# Connector.net
KiCad netlist of a schematic drawn in Altium Designer
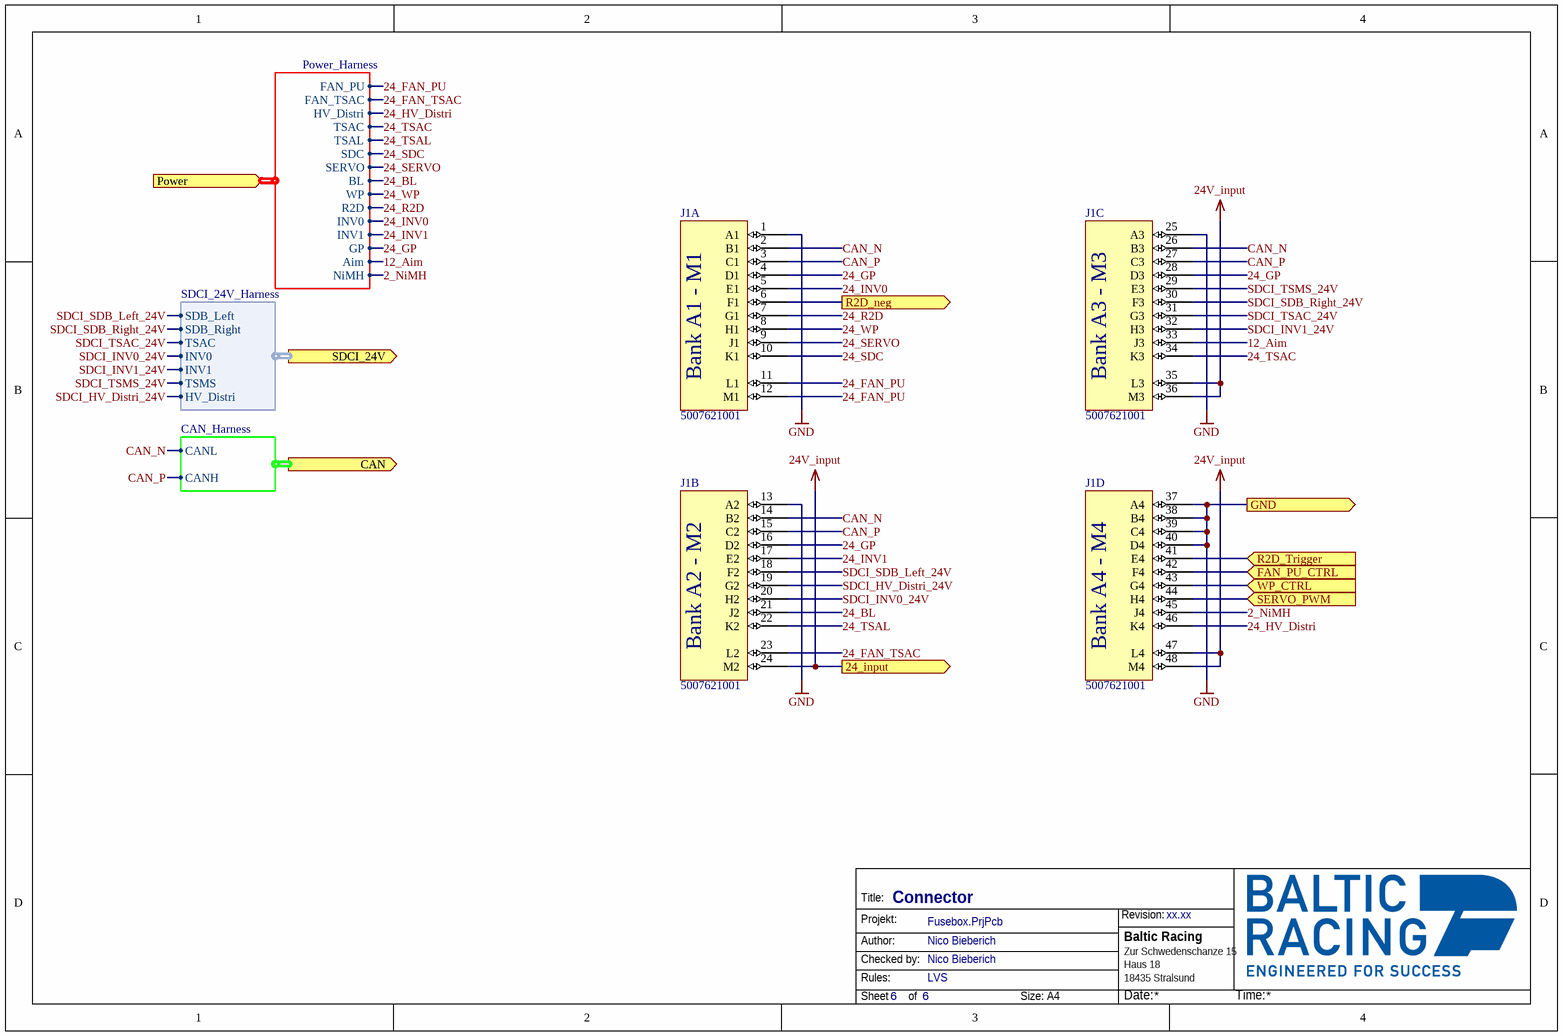
[diagram p0: Connector.SchDoc]

(export (version "E")
  (design (tool "Eeschema 10.0.6"))
  (components
    (comp (ref "J1")
      (value "5007621001")
      (footprint "5007621001")
      (description "Molex 5007621001\r\n2.50mm, 3.50mm, 3.70mm CMC Header, Sealed, Right-Angle, 48 Circuits, Black")
      (libsource (lib "libNico") (part "5007621001"))
    )
  )
  (nets
    (net (code "4") (name "/2_NiMH") (class "Default")
      (node (ref "J1") (pin "45") (pinfunction "J4_45") (pintype "bidirectional"))
    )
    (net (code "5") (name "/12_Aim") (class "Default")
      (node (ref "J1") (pin "33") (pinfunction "J3_33") (pintype "bidirectional"))
    )
    (net (code "6") (name "/24_BL") (class "Default")
      (node (ref "J1") (pin "21") (pinfunction "J2_21") (pintype "bidirectional"))
    )
    (net (code "7") (name "/24_FAN_PU") (class "Default")
      (node (ref "J1") (pin "11") (pinfunction "L1_11") (pintype "bidirectional"))
      (node (ref "J1") (pin "12") (pinfunction "M1_12") (pintype "bidirectional"))
    )
    (net (code "8") (name "/24_FAN_TSAC") (class "Default")
      (node (ref "J1") (pin "23") (pinfunction "L2_23") (pintype "bidirectional"))
    )
    (net (code "9") (name "/24_GP") (class "Default")
      (node (ref "J1") (pin "16") (pinfunction "D2_16") (pintype "bidirectional"))
      (node (ref "J1") (pin "28") (pinfunction "D3_28") (pintype "bidirectional"))
      (node (ref "J1") (pin "4") (pinfunction "D1_4") (pintype "bidirectional"))
    )
    (net (code "10") (name "/24_HV_Distri") (class "Default")
      (node (ref "J1") (pin "46") (pinfunction "K4_46") (pintype "bidirectional"))
    )
    (net (code "11") (name "/24_INV0") (class "Default")
      (node (ref "J1") (pin "5") (pinfunction "E1_5") (pintype "bidirectional"))
    )
    (net (code "12") (name "/24_INV1") (class "Default")
      (node (ref "J1") (pin "17") (pinfunction "E2_17") (pintype "bidirectional"))
    )
    (net (code "13") (name "/24_R2D") (class "Default")
      (node (ref "J1") (pin "7") (pinfunction "G1_7") (pintype "bidirectional"))
    )
    (net (code "14") (name "/24_SDC") (class "Default")
      (node (ref "J1") (pin "10") (pinfunction "K1_10") (pintype "bidirectional"))
    )
    (net (code "15") (name "/24_SERVO") (class "Default")
      (node (ref "J1") (pin "9") (pinfunction "J1_9") (pintype "bidirectional"))
    )
    (net (code "16") (name "/24_TSAC") (class "Default")
      (node (ref "J1") (pin "34") (pinfunction "K3_34") (pintype "bidirectional"))
    )
    (net (code "17") (name "/24_TSAL") (class "Default")
      (node (ref "J1") (pin "22") (pinfunction "K2_22") (pintype "bidirectional"))
    )
    (net (code "18") (name "/24_WP") (class "Default")
      (node (ref "J1") (pin "8") (pinfunction "H1_8") (pintype "bidirectional"))
    )
    (net (code "20") (name "/CAN_N") (class "Default")
      (node (ref "J1") (pin "14") (pinfunction "B2_14") (pintype "bidirectional"))
      (node (ref "J1") (pin "2") (pinfunction "B1_2") (pintype "bidirectional"))
      (node (ref "J1") (pin "26") (pinfunction "B3_26") (pintype "bidirectional"))
    )
    (net (code "21") (name "/CAN_P") (class "Default")
      (node (ref "J1") (pin "15") (pinfunction "C2_15") (pintype "bidirectional"))
      (node (ref "J1") (pin "27") (pinfunction "C3_27") (pintype "bidirectional"))
      (node (ref "J1") (pin "3") (pinfunction "C1_3") (pintype "bidirectional"))
    )
    (net (code "22") (name "/FAN_PU_CTRL") (class "Default")
      (node (ref "J1") (pin "42") (pinfunction "F4_42") (pintype "bidirectional"))
    )
    (net (code "23") (name "/R2D_Trigger") (class "Default")
      (node (ref "J1") (pin "41") (pinfunction "E4_41") (pintype "bidirectional"))
    )
    (net (code "24") (name "/R2D_neg") (class "Default")
      (node (ref "J1") (pin "6") (pinfunction "F1_6") (pintype "bidirectional"))
    )
    (net (code "25") (name "/SDCI_HV_Distri_24V") (class "Default")
      (node (ref "J1") (pin "19") (pinfunction "G2_19") (pintype "bidirectional"))
    )
    (net (code "26") (name "/SDCI_INV0_24V") (class "Default")
      (node (ref "J1") (pin "20") (pinfunction "H2_20") (pintype "bidirectional"))
    )
    (net (code "27") (name "/SDCI_INV1_24V") (class "Default")
      (node (ref "J1") (pin "32") (pinfunction "H3_32") (pintype "bidirectional"))
    )
    (net (code "28") (name "/SDCI_SDB_Left_24V") (class "Default")
      (node (ref "J1") (pin "18") (pinfunction "F2_18") (pintype "bidirectional"))
    )
    (net (code "29") (name "/SDCI_SDB_Right_24V") (class "Default")
      (node (ref "J1") (pin "30") (pinfunction "F3_30") (pintype "bidirectional"))
    )
    (net (code "30") (name "/SDCI_TSAC_24V") (class "Default")
      (node (ref "J1") (pin "31") (pinfunction "G3_31") (pintype "bidirectional"))
    )
    (net (code "31") (name "/SDCI_TSMS_24V") (class "Default")
      (node (ref "J1") (pin "29") (pinfunction "E3_29") (pintype "bidirectional"))
    )
    (net (code "32") (name "/SERVO_PWM") (class "Default")
      (node (ref "J1") (pin "44") (pinfunction "H4_44") (pintype "bidirectional"))
    )
    (net (code "33") (name "/WP_CTRL") (class "Default")
      (node (ref "J1") (pin "43") (pinfunction "G4_43") (pintype "bidirectional"))
    )
    (net (code "37") (name "24V_input") (class "Default")
      (node (ref "J1") (pin "24") (pinfunction "M2_24") (pintype "bidirectional"))
      (node (ref "J1") (pin "35") (pinfunction "L3_35") (pintype "bidirectional"))
      (node (ref "J1") (pin "36") (pinfunction "M3_36") (pintype "bidirectional"))
      (node (ref "J1") (pin "47") (pinfunction "L4_47") (pintype "bidirectional"))
      (node (ref "J1") (pin "48") (pinfunction "M4_48") (pintype "bidirectional"))
    )
    (net (code "38") (name "GND") (class "Default")
      (node (ref "J1") (pin "1") (pinfunction "A1_1") (pintype "bidirectional"))
      (node (ref "J1") (pin "13") (pinfunction "A2_13") (pintype "bidirectional"))
      (node (ref "J1") (pin "25") (pinfunction "A3_25") (pintype "bidirectional"))
      (node (ref "J1") (pin "37") (pinfunction "A4_37") (pintype "bidirectional"))
      (node (ref "J1") (pin "38") (pinfunction "B4_38") (pintype "bidirectional"))
      (node (ref "J1") (pin "39") (pinfunction "C4_39") (pintype "bidirectional"))
      (node (ref "J1") (pin "40") (pinfunction "D4_40") (pintype "bidirectional"))
    )
  )
)
